# ESD-Monitor.net
KiCad netlist of a schematic drawn in Altium Designer
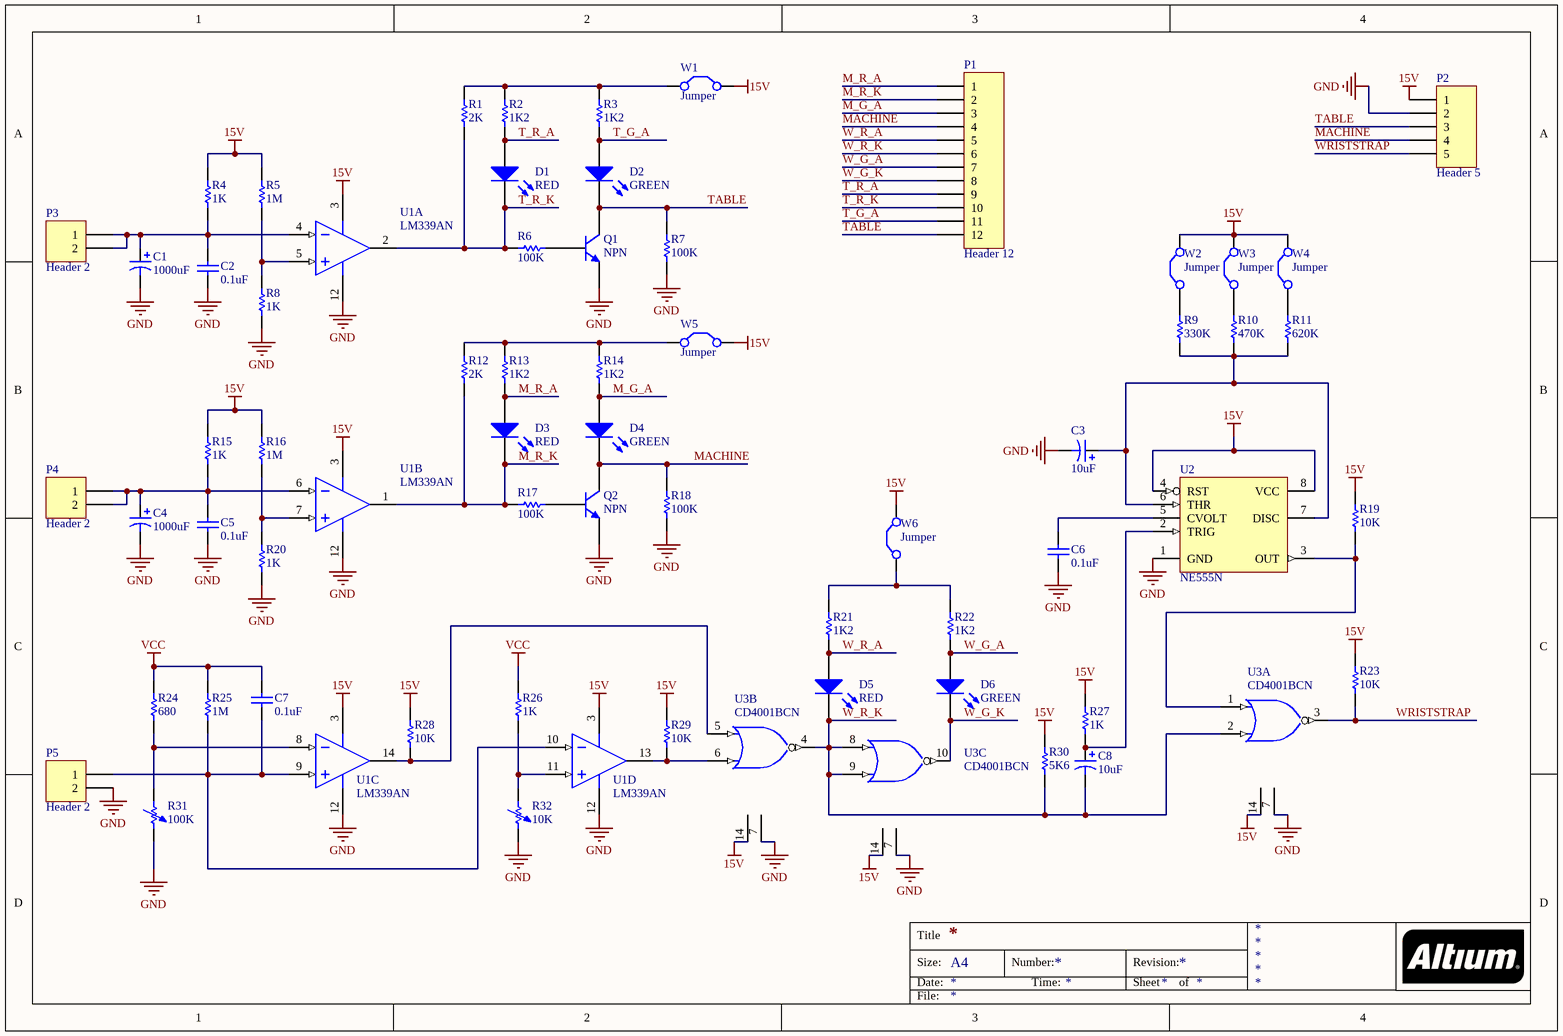
[diagram p0: ESD-Monitor.SchDoc]

(export (version "E")
  (design (tool "Eeschema 10.0.6"))
  (components
    (comp (ref "C1")
      (value "1000uF")
      (footprint "toko-Embedded:E3,5-10")
      (description "Polarized Capacitor (Radial)")
      (fields (field (name "PUBLISHER") "Altium Limited"))
      (libsource (lib "Miscellaneous Devices") (part "Cap Pol1"))
    )
    (comp (ref "C2")
      (value "0.1uF")
      (footprint "toko-Embedded:C025-024X044")
      (description "Capacitor")
      (fields (field (name "PUBLISHER") "Altium Limited"))
      (libsource (lib "Miscellaneous Devices") (part "Cap"))
    )
    (comp (ref "C3")
      (value "10uF")
      (footprint "toko-Embedded:E2,5-5")
      (description "Polarized Capacitor (Radial)")
      (fields (field (name "PUBLISHER") "Altium Limited"))
      (libsource (lib "Miscellaneous Devices") (part "Cap Pol1"))
    )
    (comp (ref "C4")
      (value "1000uF")
      (footprint "toko-Embedded:E3,5-10")
      (description "Polarized Capacitor (Radial)")
      (fields (field (name "PUBLISHER") "Altium Limited"))
      (libsource (lib "Miscellaneous Devices") (part "Cap Pol1"))
    )
    (comp (ref "C5")
      (value "0.1uF")
      (footprint "toko-Embedded:C025-024X044")
      (description "Capacitor")
      (fields (field (name "PUBLISHER") "Altium Limited"))
      (libsource (lib "Miscellaneous Devices") (part "Cap"))
    )
    (comp (ref "C6")
      (value "0.1uF")
      (footprint "toko-Embedded:C025-024X044")
      (description "Capacitor")
      (fields (field (name "PUBLISHER") "Altium Limited"))
      (libsource (lib "Miscellaneous Devices") (part "Cap"))
    )
    (comp (ref "C7")
      (value "0.1uF")
      (footprint "toko-Embedded:C025-024X044")
      (description "Capacitor")
      (fields (field (name "PUBLISHER") "Altium Limited"))
      (libsource (lib "Miscellaneous Devices") (part "Cap"))
    )
    (comp (ref "C8")
      (value "10uF")
      (footprint "toko-Embedded:E2,5-5")
      (description "Polarized Capacitor (Radial)")
      (fields (field (name "PUBLISHER") "Altium Limited"))
      (libsource (lib "Miscellaneous Devices") (part "Cap Pol1"))
    )
    (comp (ref "D1")
      (value "RED")
      (description "Typical INFRARED GaAs LED")
      (fields (field (name "PUBLISHER") "Altium Limited"))
      (libsource (lib "Miscellaneous Devices") (part "LED0"))
    )
    (comp (ref "D2")
      (value "GREEN")
      (description "Typical INFRARED GaAs LED")
      (fields (field (name "PUBLISHER") "Altium Limited"))
      (libsource (lib "Miscellaneous Devices") (part "LED0"))
    )
    (comp (ref "D3")
      (value "RED")
      (description "Typical INFRARED GaAs LED")
      (fields (field (name "PUBLISHER") "Altium Limited"))
      (libsource (lib "Miscellaneous Devices") (part "LED0"))
    )
    (comp (ref "D4")
      (value "GREEN")
      (description "Typical INFRARED GaAs LED")
      (fields (field (name "PUBLISHER") "Altium Limited"))
      (libsource (lib "Miscellaneous Devices") (part "LED0"))
    )
    (comp (ref "D5")
      (value "RED")
      (description "Typical INFRARED GaAs LED")
      (fields (field (name "PUBLISHER") "Altium Limited"))
      (libsource (lib "Miscellaneous Devices") (part "LED0"))
    )
    (comp (ref "D6")
      (value "GREEN")
      (description "Typical INFRARED GaAs LED")
      (fields (field (name "PUBLISHER") "Altium Limited"))
      (libsource (lib "Miscellaneous Devices") (part "LED0"))
    )
    (comp (ref "P1")
      (value "Header 12")
      (footprint "toko-Embedded:6410-12")
      (description "Header, 12-Pin")
      (fields (field (name "PUBLISHER") "Altium Limited"))
      (libsource (lib "Miscellaneous Connectors") (part "Header 12"))
    )
    (comp (ref "P2")
      (value "Header 5")
      (footprint "toko-Embedded:6410-05")
      (description "Header, 5-Pin")
      (fields (field (name "PUBLISHER") "Altium Limited"))
      (libsource (lib "Miscellaneous Connectors") (part "Header 5"))
    )
    (comp (ref "P3")
      (value "Header 2")
      (footprint "toko-Embedded:7395-02")
      (description "Header, 2-Pin")
      (fields (field (name "PUBLISHER") "Altium Limited"))
      (libsource (lib "Miscellaneous Connectors") (part "Header 2"))
    )
    (comp (ref "P4")
      (value "Header 2")
      (footprint "toko-Embedded:7395-02")
      (description "Header, 2-Pin")
      (fields (field (name "PUBLISHER") "Altium Limited"))
      (libsource (lib "Miscellaneous Connectors") (part "Header 2"))
    )
    (comp (ref "P5")
      (value "Header 2")
      (footprint "toko-Embedded:7395-02")
      (description "Header, 2-Pin")
      (fields (field (name "PUBLISHER") "Altium Limited"))
      (libsource (lib "Miscellaneous Connectors") (part "Header 2"))
    )
    (comp (ref "Q1")
      (value "NPN")
      (footprint "toko-Embedded:TO92")
      (description "NPN Bipolar Transistor")
      (fields (field (name "PUBLISHER") "Altium Limited"))
      (libsource (lib "Miscellaneous Devices") (part "NPN"))
    )
    (comp (ref "Q2")
      (value "NPN")
      (footprint "toko-Embedded:TO92")
      (description "NPN Bipolar Transistor")
      (fields (field (name "PUBLISHER") "Altium Limited"))
      (libsource (lib "Miscellaneous Devices") (part "NPN"))
    )
    (comp (ref "R1")
      (value "2K")
      (footprint "toko-Embedded:0207/10")
      (description "Resistor")
      (fields (field (name "PUBLISHER") "Altium Limited"))
      (libsource (lib "Miscellaneous Devices") (part "Res1"))
    )
    (comp (ref "R2")
      (value "1K2")
      (footprint "toko-Embedded:0207/10")
      (description "Resistor")
      (fields (field (name "PUBLISHER") "Altium Limited"))
      (libsource (lib "Miscellaneous Devices") (part "Res1"))
    )
    (comp (ref "R3")
      (value "1K2")
      (footprint "toko-Embedded:0207/10")
      (description "Resistor")
      (fields (field (name "PUBLISHER") "Altium Limited"))
      (libsource (lib "Miscellaneous Devices") (part "Res1"))
    )
    (comp (ref "R4")
      (value "1K")
      (footprint "toko-Embedded:0207/10")
      (description "Resistor")
      (fields (field (name "PUBLISHER") "Altium Limited"))
      (libsource (lib "Miscellaneous Devices") (part "Res1"))
    )
    (comp (ref "R5")
      (value "1M")
      (footprint "toko-Embedded:0207/10")
      (description "Resistor")
      (fields (field (name "PUBLISHER") "Altium Limited"))
      (libsource (lib "Miscellaneous Devices") (part "Res1"))
    )
    (comp (ref "R6")
      (value "100K")
      (footprint "toko-Embedded:0207/10")
      (description "Resistor")
      (fields (field (name "PUBLISHER") "Altium Limited"))
      (libsource (lib "Miscellaneous Devices") (part "Res1"))
    )
    (comp (ref "R7")
      (value "100K")
      (footprint "toko-Embedded:0207/10")
      (description "Resistor")
      (fields (field (name "PUBLISHER") "Altium Limited"))
      (libsource (lib "Miscellaneous Devices") (part "Res1"))
    )
    (comp (ref "R8")
      (value "1K")
      (footprint "toko-Embedded:0207/10")
      (description "Resistor")
      (fields (field (name "PUBLISHER") "Altium Limited"))
      (libsource (lib "Miscellaneous Devices") (part "Res1"))
    )
    (comp (ref "R9")
      (value "330K")
      (footprint "toko-Embedded:0207/10")
      (description "Resistor")
      (fields (field (name "PUBLISHER") "Altium Limited"))
      (libsource (lib "Miscellaneous Devices") (part "Res1"))
    )
    (comp (ref "R10")
      (value "470K")
      (footprint "toko-Embedded:0207/10")
      (description "Resistor")
      (fields (field (name "PUBLISHER") "Altium Limited"))
      (libsource (lib "Miscellaneous Devices") (part "Res1"))
    )
    (comp (ref "R11")
      (value "620K")
      (footprint "toko-Embedded:0207/10")
      (description "Resistor")
      (fields (field (name "PUBLISHER") "Altium Limited"))
      (libsource (lib "Miscellaneous Devices") (part "Res1"))
    )
    (comp (ref "R12")
      (value "2K")
      (footprint "toko-Embedded:0207/10")
      (description "Resistor")
      (fields (field (name "PUBLISHER") "Altium Limited"))
      (libsource (lib "Miscellaneous Devices") (part "Res1"))
    )
    (comp (ref "R13")
      (value "1K2")
      (footprint "toko-Embedded:0207/10")
      (description "Resistor")
      (fields (field (name "PUBLISHER") "Altium Limited"))
      (libsource (lib "Miscellaneous Devices") (part "Res1"))
    )
    (comp (ref "R14")
      (value "1K2")
      (footprint "toko-Embedded:0207/10")
      (description "Resistor")
      (fields (field (name "PUBLISHER") "Altium Limited"))
      (libsource (lib "Miscellaneous Devices") (part "Res1"))
    )
    (comp (ref "R15")
      (value "1K")
      (footprint "toko-Embedded:0207/10")
      (description "Resistor")
      (fields (field (name "PUBLISHER") "Altium Limited"))
      (libsource (lib "Miscellaneous Devices") (part "Res1"))
    )
    (comp (ref "R16")
      (value "1M")
      (footprint "toko-Embedded:0207/10")
      (description "Resistor")
      (fields (field (name "PUBLISHER") "Altium Limited"))
      (libsource (lib "Miscellaneous Devices") (part "Res1"))
    )
    (comp (ref "R17")
      (value "100K")
      (footprint "toko-Embedded:0207/10")
      (description "Resistor")
      (fields (field (name "PUBLISHER") "Altium Limited"))
      (libsource (lib "Miscellaneous Devices") (part "Res1"))
    )
    (comp (ref "R18")
      (value "100K")
      (footprint "toko-Embedded:0207/10")
      (description "Resistor")
      (fields (field (name "PUBLISHER") "Altium Limited"))
      (libsource (lib "Miscellaneous Devices") (part "Res1"))
    )
    (comp (ref "R19")
      (value "10K")
      (footprint "toko-Embedded:0207/10")
      (description "Resistor")
      (fields (field (name "PUBLISHER") "Altium Limited"))
      (libsource (lib "Miscellaneous Devices") (part "Res1"))
    )
    (comp (ref "R20")
      (value "1K")
      (footprint "toko-Embedded:0207/10")
      (description "Resistor")
      (fields (field (name "PUBLISHER") "Altium Limited"))
      (libsource (lib "Miscellaneous Devices") (part "Res1"))
    )
    (comp (ref "R21")
      (value "1K2")
      (footprint "toko-Embedded:0207/10")
      (description "Resistor")
      (fields (field (name "PUBLISHER") "Altium Limited"))
      (libsource (lib "Miscellaneous Devices") (part "Res1"))
    )
    (comp (ref "R22")
      (value "1K2")
      (footprint "toko-Embedded:0207/10")
      (description "Resistor")
      (fields (field (name "PUBLISHER") "Altium Limited"))
      (libsource (lib "Miscellaneous Devices") (part "Res1"))
    )
    (comp (ref "R23")
      (value "10K")
      (footprint "toko-Embedded:0207/10")
      (description "Resistor")
      (fields (field (name "PUBLISHER") "Altium Limited"))
      (libsource (lib "Miscellaneous Devices") (part "Res1"))
    )
    (comp (ref "R24")
      (value "680")
      (footprint "toko-Embedded:0207/10")
      (description "Resistor")
      (fields (field (name "PUBLISHER") "Altium Limited"))
      (libsource (lib "Miscellaneous Devices") (part "Res1"))
    )
    (comp (ref "R25")
      (value "1M")
      (footprint "toko-Embedded:0207/10")
      (description "Resistor")
      (fields (field (name "PUBLISHER") "Altium Limited"))
      (libsource (lib "Miscellaneous Devices") (part "Res1"))
    )
    (comp (ref "R26")
      (value "1K")
      (footprint "toko-Embedded:0207/10")
      (description "Resistor")
      (fields (field (name "PUBLISHER") "Altium Limited"))
      (libsource (lib "Miscellaneous Devices") (part "Res1"))
    )
    (comp (ref "R27")
      (value "1K")
      (footprint "toko-Embedded:0207/10")
      (description "Resistor")
      (fields (field (name "PUBLISHER") "Altium Limited"))
      (libsource (lib "Miscellaneous Devices") (part "Res1"))
    )
    (comp (ref "R28")
      (value "10K")
      (footprint "toko-Embedded:0207/10")
      (description "Resistor")
      (fields (field (name "PUBLISHER") "Altium Limited"))
      (libsource (lib "Miscellaneous Devices") (part "Res1"))
    )
    (comp (ref "R29")
      (value "10K")
      (footprint "toko-Embedded:0207/10")
      (description "Resistor")
      (fields (field (name "PUBLISHER") "Altium Limited"))
      (libsource (lib "Miscellaneous Devices") (part "Res1"))
    )
    (comp (ref "R30")
      (value "5K6")
      (footprint "toko-Embedded:0207/10")
      (description "Resistor")
      (fields (field (name "PUBLISHER") "Altium Limited"))
      (libsource (lib "Miscellaneous Devices") (part "Res1"))
    )
    (comp (ref "R31")
      (value "100K")
      (footprint "toko-Embedded:CA6V")
      (description "Variable Resistor")
      (fields (field (name "PUBLISHER") "Altium Limited"))
      (libsource (lib "Miscellaneous Devices") (part "Res Adj1"))
    )
    (comp (ref "R32")
      (value "10K")
      (footprint "toko-Embedded:CA6V")
      (description "Variable Resistor")
      (fields (field (name "PUBLISHER") "Altium Limited"))
      (libsource (lib "Miscellaneous Devices") (part "Res Adj1"))
    )
    (comp (ref "U1")
      (value "LM339AN")
      (footprint "646-06")
      (description "Quad Single-Supply Comparator")
      (fields (field (name "PUBLISHER") "Altium Limited"))
      (libsource (lib "Motorola Analog Comparator") (part "LM339AN"))
    )
    (comp (ref "U2")
      (value "NE555N")
      (footprint "DIP8")
      (description "General-Purpose Single Bipolar Timer")
      (fields (field (name "PUBLISHER") "Altium Limited"))
      (libsource (lib "ST Analog Timer Circuit") (part "NE555N"))
    )
    (comp (ref "U3")
      (value "CD4001BCN")
      (footprint "N14A")
      (description "Quad 2-Input NOR Buffered B series Gate, 14-Pin PDIP")
      (fields (field (name "PUBLISHER") "Altium Limited"))
      (libsource (lib "FSC Logic Gate") (part "CD4001BCN"))
    )
    (comp (ref "W1")
      (value "Jumper")
      (footprint "Miscellaneous Connectors:HDR1X2")
      (description "Jumper Wire")
      (fields (field (name "PUBLISHER") "Altium Limited"))
      (libsource (lib "Miscellaneous Devices") (part "Jumper"))
    )
    (comp (ref "W2")
      (value "Jumper")
      (footprint "Miscellaneous Connectors:HDR1X2")
      (description "Jumper Wire")
      (fields (field (name "PUBLISHER") "Altium Limited"))
      (libsource (lib "Miscellaneous Devices") (part "Jumper"))
    )
    (comp (ref "W3")
      (value "Jumper")
      (footprint "Miscellaneous Connectors:HDR1X2")
      (description "Jumper Wire")
      (fields (field (name "PUBLISHER") "Altium Limited"))
      (libsource (lib "Miscellaneous Devices") (part "Jumper"))
    )
    (comp (ref "W4")
      (value "Jumper")
      (footprint "Miscellaneous Connectors:HDR1X2")
      (description "Jumper Wire")
      (fields (field (name "PUBLISHER") "Altium Limited"))
      (libsource (lib "Miscellaneous Devices") (part "Jumper"))
    )
    (comp (ref "W5")
      (value "Jumper")
      (footprint "Miscellaneous Connectors:HDR1X2")
      (description "Jumper Wire")
      (fields (field (name "PUBLISHER") "Altium Limited"))
      (libsource (lib "Miscellaneous Devices") (part "Jumper"))
    )
    (comp (ref "W6")
      (value "Jumper")
      (footprint "Miscellaneous Connectors:HDR1X2")
      (description "Jumper Wire")
      (fields (field (name "PUBLISHER") "Altium Limited"))
      (libsource (lib "Miscellaneous Devices") (part "Jumper"))
    )
  )
  (nets
    (net (code "1") (name "/MACHINE") (class "Default")
      (node (ref "D4") (pin "2") (pinfunction "K_2") (pintype "passive"))
      (node (ref "P1") (pin "4") (pinfunction "4_4") (pintype "passive"))
      (node (ref "P2") (pin "4") (pinfunction "4_4") (pintype "passive"))
      (node (ref "Q2") (pin "1") (pinfunction "C_1") (pintype "passive"))
      (node (ref "R18") (pin "2") (pinfunction "2_2") (pintype "passive"))
    )
    (net (code "2") (name "/M_G_A") (class "Default")
      (node (ref "D4") (pin "1") (pinfunction "A_1") (pintype "passive"))
      (node (ref "P1") (pin "3") (pinfunction "3_3") (pintype "passive"))
      (node (ref "R14") (pin "1") (pinfunction "1_1") (pintype "passive"))
    )
    (net (code "3") (name "/M_R_A") (class "Default")
      (node (ref "D3") (pin "1") (pinfunction "A_1") (pintype "passive"))
      (node (ref "P1") (pin "1") (pinfunction "1_1") (pintype "passive"))
      (node (ref "R13") (pin "1") (pinfunction "1_1") (pintype "passive"))
    )
    (net (code "4") (name "/M_R_K") (class "Default")
      (node (ref "D3") (pin "2") (pinfunction "K_2") (pintype "passive"))
      (node (ref "P1") (pin "2") (pinfunction "2_2") (pintype "passive"))
      (node (ref "R12") (pin "1") (pinfunction "1_1") (pintype "passive"))
      (node (ref "R17") (pin "2") (pinfunction "2_2") (pintype "passive"))
      (node (ref "U1") (pin "1") (pinfunction "OUT_1") (pintype "open_collector"))
    )
    (net (code "5") (name "/TABLE") (class "Default")
      (node (ref "D2") (pin "2") (pinfunction "K_2") (pintype "passive"))
      (node (ref "P1") (pin "12") (pinfunction "12_12") (pintype "passive"))
      (node (ref "P2") (pin "3") (pinfunction "3_3") (pintype "passive"))
      (node (ref "Q1") (pin "1") (pinfunction "C_1") (pintype "passive"))
      (node (ref "R7") (pin "2") (pinfunction "2_2") (pintype "passive"))
    )
    (net (code "6") (name "/T_G_A") (class "Default")
      (node (ref "D2") (pin "1") (pinfunction "A_1") (pintype "passive"))
      (node (ref "P1") (pin "11") (pinfunction "11_11") (pintype "passive"))
      (node (ref "R3") (pin "1") (pinfunction "1_1") (pintype "passive"))
    )
    (net (code "7") (name "/T_R_A") (class "Default")
      (node (ref "D1") (pin "1") (pinfunction "A_1") (pintype "passive"))
      (node (ref "P1") (pin "9") (pinfunction "9_9") (pintype "passive"))
      (node (ref "R2") (pin "1") (pinfunction "1_1") (pintype "passive"))
    )
    (net (code "8") (name "/T_R_K") (class "Default")
      (node (ref "D1") (pin "2") (pinfunction "K_2") (pintype "passive"))
      (node (ref "P1") (pin "10") (pinfunction "10_10") (pintype "passive"))
      (node (ref "R1") (pin "1") (pinfunction "1_1") (pintype "passive"))
      (node (ref "R6") (pin "2") (pinfunction "2_2") (pintype "passive"))
      (node (ref "U1") (pin "2") (pinfunction "OUT_2") (pintype "open_collector"))
    )
    (net (code "9") (name "/WRISTSTRAP") (class "Default")
      (node (ref "P2") (pin "5") (pinfunction "5_5") (pintype "passive"))
      (node (ref "R23") (pin "1") (pinfunction "1_1") (pintype "passive"))
      (node (ref "U3") (pin "3") (pinfunction "J_3") (pintype "output"))
    )
    (net (code "10") (name "/W_G_A") (class "Default")
      (node (ref "D6") (pin "1") (pinfunction "A_1") (pintype "passive"))
      (node (ref "P1") (pin "7") (pinfunction "7_7") (pintype "passive"))
      (node (ref "R22") (pin "1") (pinfunction "1_1") (pintype "passive"))
    )
    (net (code "11") (name "/W_G_K") (class "Default")
      (node (ref "D6") (pin "2") (pinfunction "K_2") (pintype "passive"))
      (node (ref "P1") (pin "8") (pinfunction "8_8") (pintype "passive"))
      (node (ref "U3") (pin "10") (pinfunction "J_10") (pintype "output"))
    )
    (net (code "12") (name "/W_R_A") (class "Default")
      (node (ref "D5") (pin "1") (pinfunction "A_1") (pintype "passive"))
      (node (ref "P1") (pin "5") (pinfunction "5_5") (pintype "passive"))
      (node (ref "R21") (pin "1") (pinfunction "1_1") (pintype "passive"))
    )
    (net (code "13") (name "/W_R_K") (class "Default")
      (node (ref "C8") (pin "2") (pinfunction "2_2") (pintype "passive"))
      (node (ref "D5") (pin "2") (pinfunction "K_2") (pintype "passive"))
      (node (ref "P1") (pin "6") (pinfunction "6_6") (pintype "passive"))
      (node (ref "R30") (pin "1") (pinfunction "1_1") (pintype "passive"))
      (node (ref "U3") (pin "2") (pinfunction "B_2") (pintype "input"))
      (node (ref "U3") (pin "4") (pinfunction "J_4") (pintype "output"))
      (node (ref "U3") (pin "8") (pinfunction "A_8") (pintype "input"))
      (node (ref "U3") (pin "9") (pinfunction "B_9") (pintype "input"))
    )
    (net (code "14") (name "15V") (class "Default")
      (node (ref "P2") (pin "1") (pinfunction "1_1") (pintype "passive"))
      (node (ref "R15") (pin "2") (pinfunction "2_2") (pintype "passive"))
      (node (ref "R16") (pin "2") (pinfunction "2_2") (pintype "passive"))
      (node (ref "R19") (pin "2") (pinfunction "2_2") (pintype "passive"))
      (node (ref "R23") (pin "2") (pinfunction "2_2") (pintype "passive"))
      (node (ref "R27") (pin "2") (pinfunction "2_2") (pintype "passive"))
      (node (ref "R28") (pin "2") (pinfunction "2_2") (pintype "passive"))
      (node (ref "R29") (pin "2") (pinfunction "2_2") (pintype "passive"))
      (node (ref "R30") (pin "2") (pinfunction "2_2") (pintype "passive"))
      (node (ref "R4") (pin "2") (pinfunction "2_2") (pintype "passive"))
      (node (ref "R5") (pin "2") (pinfunction "2_2") (pintype "passive"))
      (node (ref "U1") (pin "3") (pinfunction "V+_3") (pintype "power_in"))
      (node (ref "U2") (pin "4") (pinfunction "RST_4") (pintype "input"))
      (node (ref "U2") (pin "8") (pinfunction "VCC_8") (pintype "power_in"))
      (node (ref "U3") (pin "14") (pinfunction "VDD_14") (pintype "power_in"))
      (node (ref "W1") (pin "2") (pinfunction "C2_2") (pintype "passive"))
      (node (ref "W2") (pin "2") (pinfunction "C2_2") (pintype "passive"))
      (node (ref "W3") (pin "2") (pinfunction "C2_2") (pintype "passive"))
      (node (ref "W4") (pin "2") (pinfunction "C2_2") (pintype "passive"))
      (node (ref "W5") (pin "2") (pinfunction "C2_2") (pintype "passive"))
      (node (ref "W6") (pin "2") (pinfunction "C2_2") (pintype "passive"))
    )
    (net (code "15") (name "GND") (class "Default")
      (node (ref "C1") (pin "2") (pinfunction "2_2") (pintype "passive"))
      (node (ref "C2") (pin "1") (pinfunction "1_1") (pintype "passive"))
      (node (ref "C3") (pin "2") (pinfunction "2_2") (pintype "passive"))
      (node (ref "C4") (pin "2") (pinfunction "2_2") (pintype "passive"))
      (node (ref "C5") (pin "1") (pinfunction "1_1") (pintype "passive"))
      (node (ref "C6") (pin "1") (pinfunction "1_1") (pintype "passive"))
      (node (ref "P2") (pin "2") (pinfunction "2_2") (pintype "passive"))
      (node (ref "P5") (pin "2") (pinfunction "2_2") (pintype "passive"))
      (node (ref "Q1") (pin "3") (pinfunction "E_3") (pintype "passive"))
      (node (ref "Q2") (pin "3") (pinfunction "E_3") (pintype "passive"))
      (node (ref "R18") (pin "1") (pinfunction "1_1") (pintype "passive"))
      (node (ref "R20") (pin "1") (pinfunction "1_1") (pintype "passive"))
      (node (ref "R31") (pin "2") (pinfunction "2_2") (pintype "passive"))
      (node (ref "R32") (pin "2") (pinfunction "2_2") (pintype "passive"))
      (node (ref "R7") (pin "1") (pinfunction "1_1") (pintype "passive"))
      (node (ref "R8") (pin "1") (pinfunction "1_1") (pintype "passive"))
      (node (ref "U1") (pin "12") (pinfunction "GND_12") (pintype "power_in"))
      (node (ref "U2") (pin "1") (pinfunction "GND_1") (pintype "power_in"))
      (node (ref "U3") (pin "7") (pinfunction "GND_7") (pintype "power_in"))
    )
    (net (code "16") (name "Net-(Q1-B)") (class "Default")
      (node (ref "Q1") (pin "2") (pinfunction "B_2") (pintype "passive"))
      (node (ref "R6") (pin "1") (pinfunction "1_1") (pintype "passive"))
    )
    (net (code "17") (name "Net-(Q2-B)") (class "Default")
      (node (ref "Q2") (pin "2") (pinfunction "B_2") (pintype "passive"))
      (node (ref "R17") (pin "1") (pinfunction "1_1") (pintype "passive"))
    )
    (net (code "18") (name "Net-(U1A-IN+)") (class "Default")
      (node (ref "R5") (pin "1") (pinfunction "1_1") (pintype "passive"))
      (node (ref "R8") (pin "2") (pinfunction "2_2") (pintype "passive"))
      (node (ref "U1") (pin "5") (pinfunction "IN+_5") (pintype "input"))
    )
    (net (code "19") (name "Net-(U1A-IN-)") (class "Default")
      (node (ref "C1") (pin "1") (pinfunction "1_1") (pintype "passive"))
      (node (ref "C2") (pin "2") (pinfunction "2_2") (pintype "passive"))
      (node (ref "P3") (pin "1") (pinfunction "1_1") (pintype "passive"))
      (node (ref "P3") (pin "2") (pinfunction "2_2") (pintype "passive"))
      (node (ref "R4") (pin "1") (pinfunction "1_1") (pintype "passive"))
      (node (ref "U1") (pin "4") (pinfunction "IN-_4") (pintype "input"))
    )
    (net (code "20") (name "Net-(U1B-IN+)") (class "Default")
      (node (ref "R16") (pin "1") (pinfunction "1_1") (pintype "passive"))
      (node (ref "R20") (pin "2") (pinfunction "2_2") (pintype "passive"))
      (node (ref "U1") (pin "7") (pinfunction "IN+_7") (pintype "input"))
    )
    (net (code "21") (name "Net-(U1B-IN-)") (class "Default")
      (node (ref "C4") (pin "1") (pinfunction "1_1") (pintype "passive"))
      (node (ref "C5") (pin "2") (pinfunction "2_2") (pintype "passive"))
      (node (ref "P4") (pin "1") (pinfunction "1_1") (pintype "passive"))
      (node (ref "P4") (pin "2") (pinfunction "2_2") (pintype "passive"))
      (node (ref "R15") (pin "1") (pinfunction "1_1") (pintype "passive"))
      (node (ref "U1") (pin "6") (pinfunction "IN-_6") (pintype "input"))
    )
    (net (code "22") (name "Net-(U1C-IN+)") (class "Default")
      (node (ref "C7") (pin "1") (pinfunction "1_1") (pintype "passive"))
      (node (ref "P5") (pin "1") (pinfunction "1_1") (pintype "passive"))
      (node (ref "R25") (pin "1") (pinfunction "1_1") (pintype "passive"))
      (node (ref "U1") (pin "10") (pinfunction "IN-_10") (pintype "input"))
      (node (ref "U1") (pin "9") (pinfunction "IN+_9") (pintype "input"))
    )
    (net (code "23") (name "Net-(U1C-IN-)") (class "Default")
      (node (ref "R24") (pin "1") (pinfunction "1_1") (pintype "passive"))
      (node (ref "R31") (pin "1") (pinfunction "1_1") (pintype "passive"))
      (node (ref "U1") (pin "8") (pinfunction "IN-_8") (pintype "input"))
    )
    (net (code "24") (name "Net-(U1C-OUT)") (class "Default")
      (node (ref "R28") (pin "1") (pinfunction "1_1") (pintype "passive"))
      (node (ref "U1") (pin "14") (pinfunction "OUT_14") (pintype "open_collector"))
      (node (ref "U3") (pin "5") (pinfunction "A_5") (pintype "input"))
    )
    (net (code "25") (name "Net-(U1D-IN+)") (class "Default")
      (node (ref "R26") (pin "1") (pinfunction "1_1") (pintype "passive"))
      (node (ref "R32") (pin "1") (pinfunction "1_1") (pintype "passive"))
      (node (ref "U1") (pin "11") (pinfunction "IN+_11") (pintype "input"))
    )
    (net (code "26") (name "Net-(U1D-OUT)") (class "Default")
      (node (ref "R29") (pin "1") (pinfunction "1_1") (pintype "passive"))
      (node (ref "U1") (pin "13") (pinfunction "OUT_13") (pintype "open_collector"))
      (node (ref "U3") (pin "6") (pinfunction "B_6") (pintype "input"))
    )
    (net (code "27") (name "Net-(U2-CVOLT)") (class "Default")
      (node (ref "C6") (pin "2") (pinfunction "2_2") (pintype "passive"))
      (node (ref "U2") (pin "5") (pinfunction "CVOLT_5") (pintype "passive"))
    )
    (net (code "28") (name "Net-(U2-DISC)") (class "Default")
      (node (ref "C3") (pin "1") (pinfunction "1_1") (pintype "passive"))
      (node (ref "R10") (pin "1") (pinfunction "1_1") (pintype "passive"))
      (node (ref "R11") (pin "1") (pinfunction "1_1") (pintype "passive"))
      (node (ref "R9") (pin "1") (pinfunction "1_1") (pintype "passive"))
      (node (ref "U2") (pin "6") (pinfunction "THR_6") (pintype "input"))
      (node (ref "U2") (pin "7") (pinfunction "DISC_7") (pintype "open_collector"))
    )
    (net (code "29") (name "Net-(U2-OUT)") (class "Default")
      (node (ref "R19") (pin "1") (pinfunction "1_1") (pintype "passive"))
      (node (ref "U2") (pin "3") (pinfunction "OUT_3") (pintype "output"))
      (node (ref "U3") (pin "1") (pinfunction "A_1") (pintype "input"))
    )
    (net (code "30") (name "Net-(U2-TRIG)") (class "Default")
      (node (ref "C8") (pin "1") (pinfunction "1_1") (pintype "passive"))
      (node (ref "R27") (pin "1") (pinfunction "1_1") (pintype "passive"))
      (node (ref "U2") (pin "2") (pinfunction "TRIG_2") (pintype "input"))
    )
    (net (code "31") (name "Net-(W1-C1)") (class "Default")
      (node (ref "R1") (pin "2") (pinfunction "2_2") (pintype "passive"))
      (node (ref "R2") (pin "2") (pinfunction "2_2") (pintype "passive"))
      (node (ref "R3") (pin "2") (pinfunction "2_2") (pintype "passive"))
      (node (ref "W1") (pin "1") (pinfunction "C1_1") (pintype "passive"))
    )
    (net (code "32") (name "Net-(W2-C1)") (class "Default")
      (node (ref "R9") (pin "2") (pinfunction "2_2") (pintype "passive"))
      (node (ref "W2") (pin "1") (pinfunction "C1_1") (pintype "passive"))
    )
    (net (code "33") (name "Net-(W3-C1)") (class "Default")
      (node (ref "R10") (pin "2") (pinfunction "2_2") (pintype "passive"))
      (node (ref "W3") (pin "1") (pinfunction "C1_1") (pintype "passive"))
    )
    (net (code "34") (name "Net-(W4-C1)") (class "Default")
      (node (ref "R11") (pin "2") (pinfunction "2_2") (pintype "passive"))
      (node (ref "W4") (pin "1") (pinfunction "C1_1") (pintype "passive"))
    )
    (net (code "35") (name "Net-(W5-C1)") (class "Default")
      (node (ref "R12") (pin "2") (pinfunction "2_2") (pintype "passive"))
      (node (ref "R13") (pin "2") (pinfunction "2_2") (pintype "passive"))
      (node (ref "R14") (pin "2") (pinfunction "2_2") (pintype "passive"))
      (node (ref "W5") (pin "1") (pinfunction "C1_1") (pintype "passive"))
    )
    (net (code "36") (name "Net-(W6-C1)") (class "Default")
      (node (ref "R21") (pin "2") (pinfunction "2_2") (pintype "passive"))
      (node (ref "R22") (pin "2") (pinfunction "2_2") (pintype "passive"))
      (node (ref "W6") (pin "1") (pinfunction "C1_1") (pintype "passive"))
    )
    (net (code "37") (name "VCC") (class "Default")
      (node (ref "C7") (pin "2") (pinfunction "2_2") (pintype "passive"))
      (node (ref "R24") (pin "2") (pinfunction "2_2") (pintype "passive"))
      (node (ref "R25") (pin "2") (pinfunction "2_2") (pintype "passive"))
      (node (ref "R26") (pin "2") (pinfunction "2_2") (pintype "passive"))
    )
  )
)
